# minime_mini_2_1.net
KiCad netlist of a schematic drawn in EAGLE
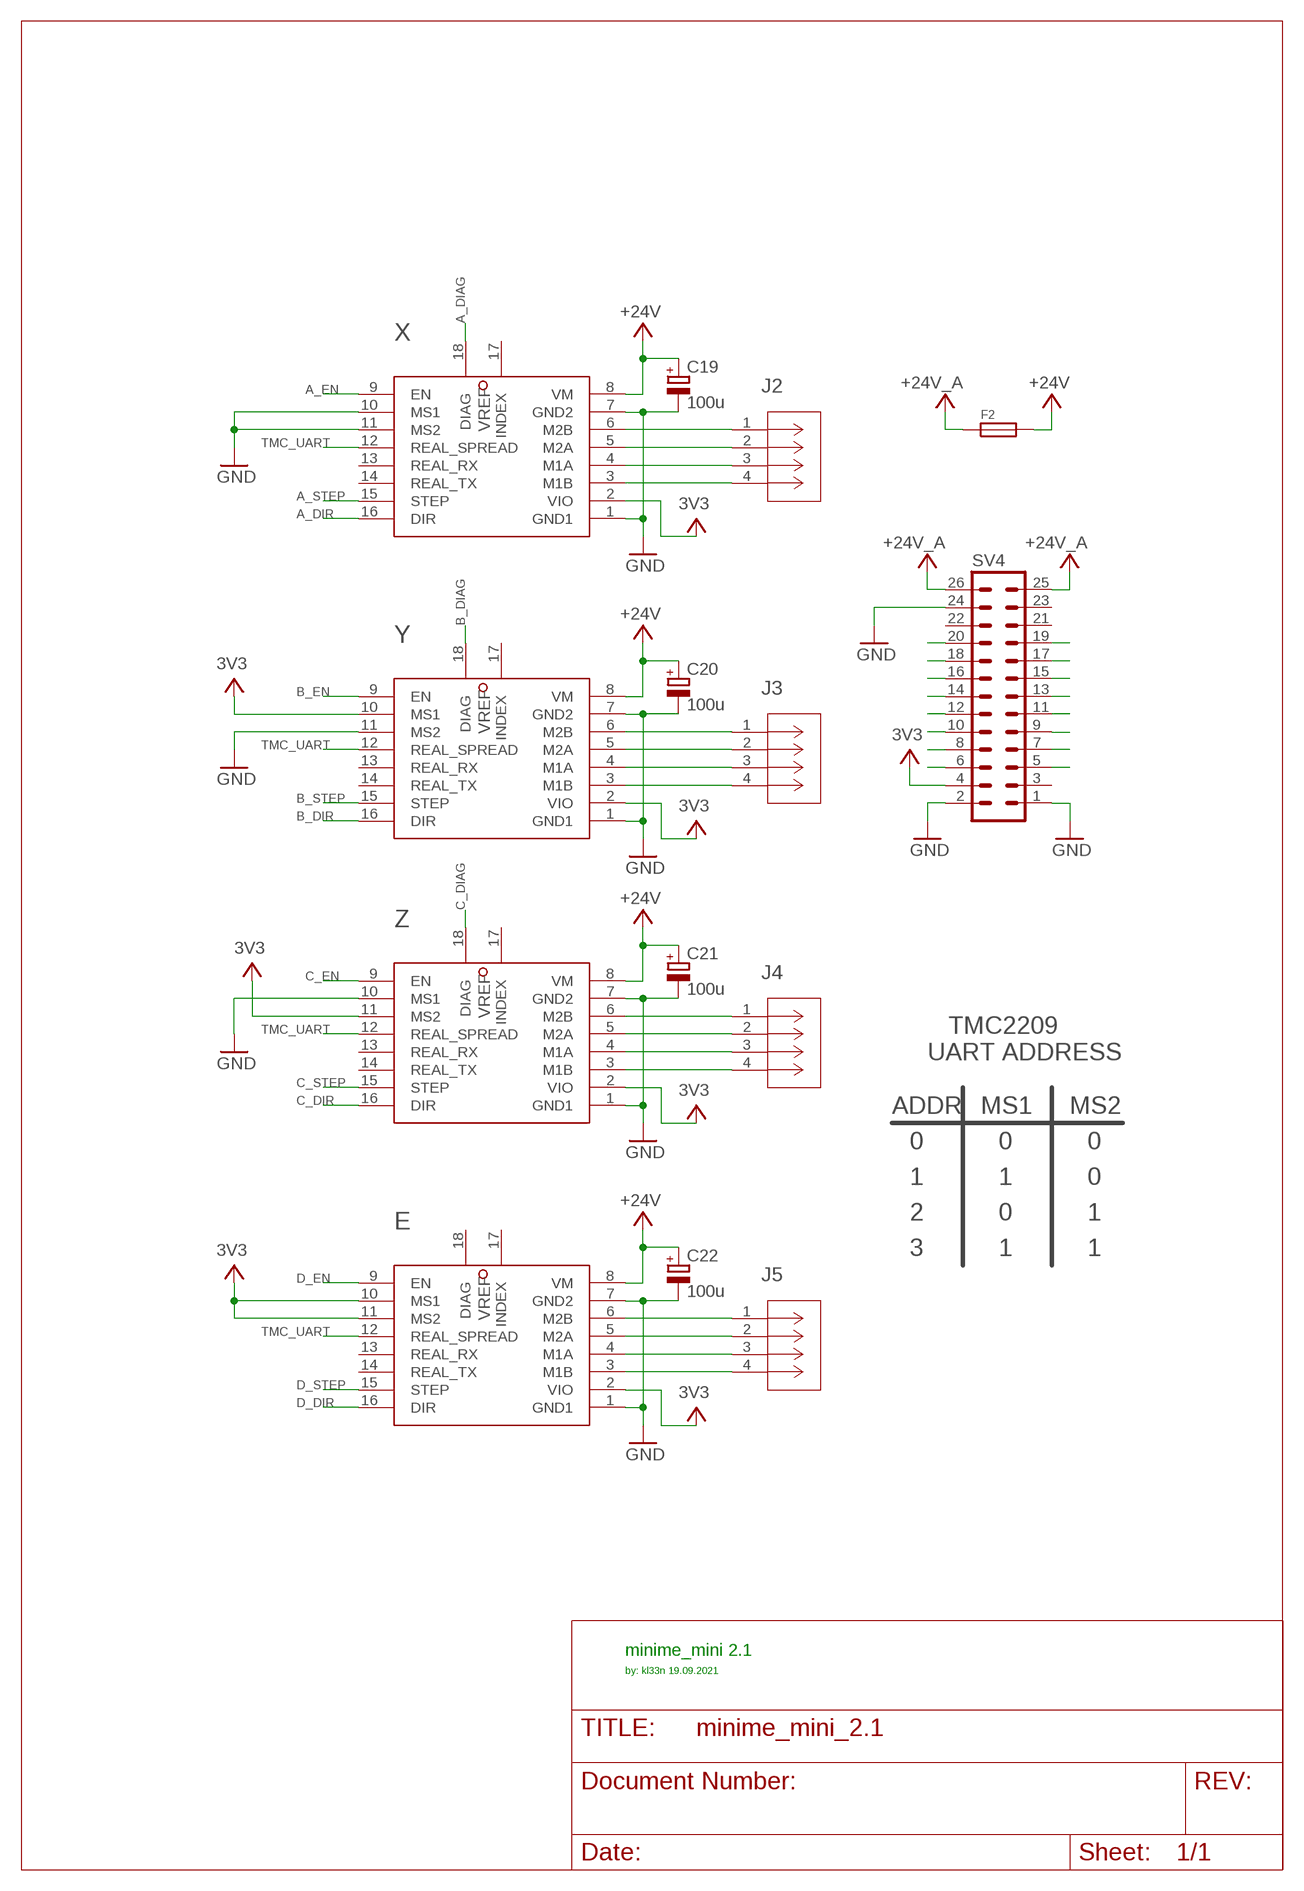
[diagram p0: schematic, sheet 1]

(export (version "E")
  (design (tool "Eeschema 10.0.6"))
  (components
    (comp (ref "C19")
      (value "100u")
      (footprint "eagle-import:175TMP-0810")
      (libsource (lib "eagle-import") (part "CPOL-EU175TMP-0810"))
    )
    (comp (ref "C20")
      (value "100u")
      (footprint "eagle-import:175TMP-0810")
      (libsource (lib "eagle-import") (part "CPOL-EU175TMP-0810"))
    )
    (comp (ref "C21")
      (value "100u")
      (footprint "eagle-import:175TMP-0810")
      (libsource (lib "eagle-import") (part "CPOL-EU175TMP-0810"))
    )
    (comp (ref "C22")
      (value "100u")
      (footprint "eagle-import:175TMP-0810")
      (libsource (lib "eagle-import") (part "CPOL-EU175TMP-0810"))
    )
    (comp (ref "F2")
      (value "FUSE/SERIE154")
      (footprint "eagle-import:FUSE_NANO-OMNI")
      (libsource (lib "eagle-import") (part "FUSE/SERIE154"))
    )
    (comp (ref "J2")
      (value "B4B-XH-AM(LF)(SN)")
      (footprint "eagle-import:CONN_B4B-XH-AM_JST")
      (fields (field (name "COPYRIGHT") "Copyright (C) 2018 Accelerated Designs. All rights reserved"))
      (libsource (lib "eagle-import") (part "B4B-XH-AM(LF)(SN)"))
    )
    (comp (ref "J3")
      (value "B4B-XH-AM(LF)(SN)")
      (footprint "eagle-import:CONN_B4B-XH-AM_JST")
      (fields (field (name "COPYRIGHT") "Copyright (C) 2018 Accelerated Designs. All rights reserved"))
      (libsource (lib "eagle-import") (part "B4B-XH-AM(LF)(SN)"))
    )
    (comp (ref "J4")
      (value "B4B-XH-AM(LF)(SN)")
      (footprint "eagle-import:CONN_B4B-XH-AM_JST")
      (fields (field (name "COPYRIGHT") "Copyright (C) 2018 Accelerated Designs. All rights reserved"))
      (libsource (lib "eagle-import") (part "B4B-XH-AM(LF)(SN)"))
    )
    (comp (ref "J5")
      (value "B4B-XH-AM(LF)(SN)")
      (footprint "eagle-import:CONN_B4B-XH-AM_JST")
      (fields (field (name "COPYRIGHT") "Copyright (C) 2018 Accelerated Designs. All rights reserved"))
      (libsource (lib "eagle-import") (part "B4B-XH-AM(LF)(SN)"))
    )
    (comp (ref "SV4")
      (value "MA13-2")
      (footprint "eagle-import:MA13-2")
      (libsource (lib "eagle-import") (part "MA13-2"))
    )
    (comp (ref "U$1")
      (value "TMC2209")
      (footprint "eagle-import:TMC2209")
      (libsource (lib "eagle-import") (part "TMC2209"))
    )
    (comp (ref "U$2")
      (value "TMC2209")
      (footprint "eagle-import:TMC2209")
      (libsource (lib "eagle-import") (part "TMC2209"))
    )
    (comp (ref "U$3")
      (value "TMC2209")
      (footprint "eagle-import:TMC2209")
      (libsource (lib "eagle-import") (part "TMC2209"))
    )
    (comp (ref "U$4")
      (value "TMC2209")
      (footprint "eagle-import:TMC2209")
      (libsource (lib "eagle-import") (part "TMC2209"))
    )
  )
  (nets
    (net (code "1") (name "+24V") (class "Default")
      (node (ref "C19") (pin "+") (pinfunction "+_+") (pintype "passive"))
      (node (ref "C20") (pin "+") (pinfunction "+_+") (pintype "passive"))
      (node (ref "C21") (pin "+") (pinfunction "+_+") (pintype "passive"))
      (node (ref "C22") (pin "+") (pinfunction "+_+") (pintype "passive"))
      (node (ref "F2") (pin "2") (pinfunction "2_2") (pintype "passive"))
      (node (ref "U$1") (pin "8") (pinfunction "VM_8") (pintype "bidirectional"))
      (node (ref "U$2") (pin "8") (pinfunction "VM_8") (pintype "bidirectional"))
      (node (ref "U$3") (pin "8") (pinfunction "VM_8") (pintype "bidirectional"))
      (node (ref "U$4") (pin "8") (pinfunction "VM_8") (pintype "bidirectional"))
    )
    (net (code "2") (name "+24V_A") (class "Default")
      (node (ref "F2") (pin "1") (pinfunction "1_1") (pintype "passive"))
      (node (ref "SV4") (pin "25") (pinfunction "25_25") (pintype "passive"))
      (node (ref "SV4") (pin "26") (pinfunction "26_26") (pintype "passive"))
    )
    (net (code "3") (name "/A_DIAG") (class "Default")
      (node (ref "SV4") (pin "5") (pinfunction "5_5") (pintype "passive"))
      (node (ref "U$2") (pin "18") (pinfunction "DIAG_18") (pintype "bidirectional"))
    )
    (net (code "4") (name "/A_DIR") (class "Default")
      (node (ref "SV4") (pin "8") (pinfunction "8_8") (pintype "passive"))
      (node (ref "U$2") (pin "16") (pinfunction "DIR_16") (pintype "bidirectional"))
    )
    (net (code "5") (name "/A_EN") (class "Default")
      (node (ref "SV4") (pin "6") (pinfunction "6_6") (pintype "passive"))
      (node (ref "U$2") (pin "9") (pinfunction "EN_9") (pintype "bidirectional"))
    )
    (net (code "6") (name "/A_STEP") (class "Default")
      (node (ref "SV4") (pin "7") (pinfunction "7_7") (pintype "passive"))
      (node (ref "U$2") (pin "15") (pinfunction "STEP_15") (pintype "bidirectional"))
    )
    (net (code "7") (name "/B_DIAG") (class "Default")
      (node (ref "SV4") (pin "14") (pinfunction "14_14") (pintype "passive"))
      (node (ref "U$1") (pin "18") (pinfunction "DIAG_18") (pintype "bidirectional"))
    )
    (net (code "8") (name "/B_DIR") (class "Default")
      (node (ref "SV4") (pin "17") (pinfunction "17_17") (pintype "passive"))
      (node (ref "U$1") (pin "16") (pinfunction "DIR_16") (pintype "bidirectional"))
    )
    (net (code "9") (name "/B_EN") (class "Default")
      (node (ref "SV4") (pin "15") (pinfunction "15_15") (pintype "passive"))
      (node (ref "U$1") (pin "9") (pinfunction "EN_9") (pintype "bidirectional"))
    )
    (net (code "10") (name "/B_STEP") (class "Default")
      (node (ref "SV4") (pin "16") (pinfunction "16_16") (pintype "passive"))
      (node (ref "U$1") (pin "15") (pinfunction "STEP_15") (pintype "bidirectional"))
    )
    (net (code "11") (name "/C_DIAG") (class "Default")
      (node (ref "SV4") (pin "9") (pinfunction "9_9") (pintype "passive"))
      (node (ref "U$3") (pin "18") (pinfunction "DIAG_18") (pintype "bidirectional"))
    )
    (net (code "12") (name "/C_DIR") (class "Default")
      (node (ref "SV4") (pin "12") (pinfunction "12_12") (pintype "passive"))
      (node (ref "U$3") (pin "16") (pinfunction "DIR_16") (pintype "bidirectional"))
    )
    (net (code "13") (name "/C_EN") (class "Default")
      (node (ref "SV4") (pin "10") (pinfunction "10_10") (pintype "passive"))
      (node (ref "U$3") (pin "9") (pinfunction "EN_9") (pintype "bidirectional"))
    )
    (net (code "14") (name "/C_STEP") (class "Default")
      (node (ref "SV4") (pin "11") (pinfunction "11_11") (pintype "passive"))
      (node (ref "U$3") (pin "15") (pinfunction "STEP_15") (pintype "bidirectional"))
    )
    (net (code "15") (name "/D_DIR") (class "Default")
      (node (ref "SV4") (pin "20") (pinfunction "20_20") (pintype "passive"))
      (node (ref "U$4") (pin "16") (pinfunction "DIR_16") (pintype "bidirectional"))
    )
    (net (code "16") (name "/D_EN") (class "Default")
      (node (ref "SV4") (pin "18") (pinfunction "18_18") (pintype "passive"))
      (node (ref "U$4") (pin "9") (pinfunction "EN_9") (pintype "bidirectional"))
    )
    (net (code "17") (name "/D_STEP") (class "Default")
      (node (ref "SV4") (pin "19") (pinfunction "19_19") (pintype "passive"))
      (node (ref "U$4") (pin "15") (pinfunction "STEP_15") (pintype "bidirectional"))
    )
    (net (code "18") (name "/TMC_UART") (class "Default")
      (node (ref "SV4") (pin "13") (pinfunction "13_13") (pintype "passive"))
      (node (ref "U$1") (pin "12") (pinfunction "REAL_SPREAD_12") (pintype "bidirectional"))
      (node (ref "U$2") (pin "12") (pinfunction "REAL_SPREAD_12") (pintype "bidirectional"))
      (node (ref "U$3") (pin "12") (pinfunction "REAL_SPREAD_12") (pintype "bidirectional"))
      (node (ref "U$4") (pin "12") (pinfunction "REAL_SPREAD_12") (pintype "bidirectional"))
    )
    (net (code "19") (name "3V3") (class "Default")
      (node (ref "SV4") (pin "4") (pinfunction "4_4") (pintype "passive"))
      (node (ref "U$1") (pin "10") (pinfunction "MS1_10") (pintype "bidirectional"))
      (node (ref "U$1") (pin "2") (pinfunction "VIO_2") (pintype "bidirectional"))
      (node (ref "U$2") (pin "2") (pinfunction "VIO_2") (pintype "bidirectional"))
      (node (ref "U$3") (pin "11") (pinfunction "MS2_11") (pintype "bidirectional"))
      (node (ref "U$3") (pin "2") (pinfunction "VIO_2") (pintype "bidirectional"))
      (node (ref "U$4") (pin "10") (pinfunction "MS1_10") (pintype "bidirectional"))
      (node (ref "U$4") (pin "11") (pinfunction "MS2_11") (pintype "bidirectional"))
      (node (ref "U$4") (pin "2") (pinfunction "VIO_2") (pintype "bidirectional"))
    )
    (net (code "20") (name "GND") (class "Default")
      (node (ref "C19") (pin "-") (pinfunction "-_-") (pintype "passive"))
      (node (ref "C20") (pin "-") (pinfunction "-_-") (pintype "passive"))
      (node (ref "C21") (pin "-") (pinfunction "-_-") (pintype "passive"))
      (node (ref "C22") (pin "-") (pinfunction "-_-") (pintype "passive"))
      (node (ref "SV4") (pin "1") (pinfunction "1_1") (pintype "passive"))
      (node (ref "SV4") (pin "2") (pinfunction "2_2") (pintype "passive"))
      (node (ref "SV4") (pin "24") (pinfunction "24_24") (pintype "passive"))
      (node (ref "U$1") (pin "1") (pinfunction "GND1_1") (pintype "bidirectional"))
      (node (ref "U$1") (pin "11") (pinfunction "MS2_11") (pintype "bidirectional"))
      (node (ref "U$1") (pin "7") (pinfunction "GND2_7") (pintype "bidirectional"))
      (node (ref "U$2") (pin "1") (pinfunction "GND1_1") (pintype "bidirectional"))
      (node (ref "U$2") (pin "10") (pinfunction "MS1_10") (pintype "bidirectional"))
      (node (ref "U$2") (pin "11") (pinfunction "MS2_11") (pintype "bidirectional"))
      (node (ref "U$2") (pin "7") (pinfunction "GND2_7") (pintype "bidirectional"))
      (node (ref "U$3") (pin "1") (pinfunction "GND1_1") (pintype "bidirectional"))
      (node (ref "U$3") (pin "10") (pinfunction "MS1_10") (pintype "bidirectional"))
      (node (ref "U$3") (pin "7") (pinfunction "GND2_7") (pintype "bidirectional"))
      (node (ref "U$4") (pin "1") (pinfunction "GND1_1") (pintype "bidirectional"))
      (node (ref "U$4") (pin "7") (pinfunction "GND2_7") (pintype "bidirectional"))
    )
    (net (code "21") (name "Net-(U$1-M1A)") (class "Default")
      (node (ref "J3") (pin "3") (pinfunction "3_3") (pintype "passive"))
      (node (ref "U$1") (pin "4") (pinfunction "M1A_4") (pintype "bidirectional"))
    )
    (net (code "22") (name "Net-(U$1-M1B)") (class "Default")
      (node (ref "J3") (pin "4") (pinfunction "4_4") (pintype "passive"))
      (node (ref "U$1") (pin "3") (pinfunction "M1B_3") (pintype "bidirectional"))
    )
    (net (code "23") (name "Net-(U$1-M2A)") (class "Default")
      (node (ref "J3") (pin "2") (pinfunction "2_2") (pintype "passive"))
      (node (ref "U$1") (pin "5") (pinfunction "M2A_5") (pintype "bidirectional"))
    )
    (net (code "24") (name "Net-(U$1-M2B)") (class "Default")
      (node (ref "J3") (pin "1") (pinfunction "1_1") (pintype "passive"))
      (node (ref "U$1") (pin "6") (pinfunction "M2B_6") (pintype "bidirectional"))
    )
    (net (code "25") (name "Net-(U$2-M1A)") (class "Default")
      (node (ref "J2") (pin "3") (pinfunction "3_3") (pintype "passive"))
      (node (ref "U$2") (pin "4") (pinfunction "M1A_4") (pintype "bidirectional"))
    )
    (net (code "26") (name "Net-(U$2-M1B)") (class "Default")
      (node (ref "J2") (pin "4") (pinfunction "4_4") (pintype "passive"))
      (node (ref "U$2") (pin "3") (pinfunction "M1B_3") (pintype "bidirectional"))
    )
    (net (code "27") (name "Net-(U$2-M2A)") (class "Default")
      (node (ref "J2") (pin "2") (pinfunction "2_2") (pintype "passive"))
      (node (ref "U$2") (pin "5") (pinfunction "M2A_5") (pintype "bidirectional"))
    )
    (net (code "28") (name "Net-(U$2-M2B)") (class "Default")
      (node (ref "J2") (pin "1") (pinfunction "1_1") (pintype "passive"))
      (node (ref "U$2") (pin "6") (pinfunction "M2B_6") (pintype "bidirectional"))
    )
    (net (code "29") (name "Net-(U$3-M1A)") (class "Default")
      (node (ref "J4") (pin "3") (pinfunction "3_3") (pintype "passive"))
      (node (ref "U$3") (pin "4") (pinfunction "M1A_4") (pintype "bidirectional"))
    )
    (net (code "30") (name "Net-(U$3-M1B)") (class "Default")
      (node (ref "J4") (pin "4") (pinfunction "4_4") (pintype "passive"))
      (node (ref "U$3") (pin "3") (pinfunction "M1B_3") (pintype "bidirectional"))
    )
    (net (code "31") (name "Net-(U$3-M2A)") (class "Default")
      (node (ref "J4") (pin "2") (pinfunction "2_2") (pintype "passive"))
      (node (ref "U$3") (pin "5") (pinfunction "M2A_5") (pintype "bidirectional"))
    )
    (net (code "32") (name "Net-(U$3-M2B)") (class "Default")
      (node (ref "J4") (pin "1") (pinfunction "1_1") (pintype "passive"))
      (node (ref "U$3") (pin "6") (pinfunction "M2B_6") (pintype "bidirectional"))
    )
    (net (code "33") (name "Net-(U$4-M1A)") (class "Default")
      (node (ref "J5") (pin "3") (pinfunction "3_3") (pintype "passive"))
      (node (ref "U$4") (pin "4") (pinfunction "M1A_4") (pintype "bidirectional"))
    )
    (net (code "34") (name "Net-(U$4-M1B)") (class "Default")
      (node (ref "J5") (pin "4") (pinfunction "4_4") (pintype "passive"))
      (node (ref "U$4") (pin "3") (pinfunction "M1B_3") (pintype "bidirectional"))
    )
    (net (code "35") (name "Net-(U$4-M2A)") (class "Default")
      (node (ref "J5") (pin "2") (pinfunction "2_2") (pintype "passive"))
      (node (ref "U$4") (pin "5") (pinfunction "M2A_5") (pintype "bidirectional"))
    )
    (net (code "36") (name "Net-(U$4-M2B)") (class "Default")
      (node (ref "J5") (pin "1") (pinfunction "1_1") (pintype "passive"))
      (node (ref "U$4") (pin "6") (pinfunction "M2B_6") (pintype "bidirectional"))
    )
    (net (code "37") (name "unconnected-(SV4-Pad3)") (class "Default")
      (node (ref "SV4") (pin "3") (pinfunction "3_3") (pintype "passive"))
    )
    (net (code "38") (name "unconnected-(SV4-Pad21)") (class "Default")
      (node (ref "SV4") (pin "21") (pinfunction "21_21") (pintype "passive"))
    )
    (net (code "39") (name "unconnected-(SV4-Pad22)") (class "Default")
      (node (ref "SV4") (pin "22") (pinfunction "22_22") (pintype "passive"))
    )
    (net (code "40") (name "unconnected-(SV4-Pad23)") (class "Default")
      (node (ref "SV4") (pin "23") (pinfunction "23_23") (pintype "passive"))
    )
    (net (code "41") (name "unconnected-(U$1-INDEX-Pad17)") (class "Default")
      (node (ref "U$1") (pin "17") (pinfunction "INDEX_17") (pintype "bidirectional"))
    )
    (net (code "42") (name "unconnected-(U$1-REAL_RX-Pad13)") (class "Default")
      (node (ref "U$1") (pin "13") (pinfunction "REAL_RX_13") (pintype "bidirectional"))
    )
    (net (code "43") (name "unconnected-(U$1-REAL_TX-Pad14)") (class "Default")
      (node (ref "U$1") (pin "14") (pinfunction "REAL_TX_14") (pintype "bidirectional"))
    )
    (net (code "44") (name "unconnected-(U$2-INDEX-Pad17)") (class "Default")
      (node (ref "U$2") (pin "17") (pinfunction "INDEX_17") (pintype "bidirectional"))
    )
    (net (code "45") (name "unconnected-(U$2-REAL_RX-Pad13)") (class "Default")
      (node (ref "U$2") (pin "13") (pinfunction "REAL_RX_13") (pintype "bidirectional"))
    )
    (net (code "46") (name "unconnected-(U$2-REAL_TX-Pad14)") (class "Default")
      (node (ref "U$2") (pin "14") (pinfunction "REAL_TX_14") (pintype "bidirectional"))
    )
    (net (code "47") (name "unconnected-(U$3-INDEX-Pad17)") (class "Default")
      (node (ref "U$3") (pin "17") (pinfunction "INDEX_17") (pintype "bidirectional"))
    )
    (net (code "48") (name "unconnected-(U$3-REAL_RX-Pad13)") (class "Default")
      (node (ref "U$3") (pin "13") (pinfunction "REAL_RX_13") (pintype "bidirectional"))
    )
    (net (code "49") (name "unconnected-(U$3-REAL_TX-Pad14)") (class "Default")
      (node (ref "U$3") (pin "14") (pinfunction "REAL_TX_14") (pintype "bidirectional"))
    )
    (net (code "50") (name "unconnected-(U$4-DIAG-Pad18)") (class "Default")
      (node (ref "U$4") (pin "18") (pinfunction "DIAG_18") (pintype "bidirectional"))
    )
    (net (code "51") (name "unconnected-(U$4-INDEX-Pad17)") (class "Default")
      (node (ref "U$4") (pin "17") (pinfunction "INDEX_17") (pintype "bidirectional"))
    )
    (net (code "52") (name "unconnected-(U$4-REAL_RX-Pad13)") (class "Default")
      (node (ref "U$4") (pin "13") (pinfunction "REAL_RX_13") (pintype "bidirectional"))
    )
    (net (code "53") (name "unconnected-(U$4-REAL_TX-Pad14)") (class "Default")
      (node (ref "U$4") (pin "14") (pinfunction "REAL_TX_14") (pintype "bidirectional"))
    )
  )
)
